# SensorPCB.net
KiCad netlist of a schematic drawn in EAGLE
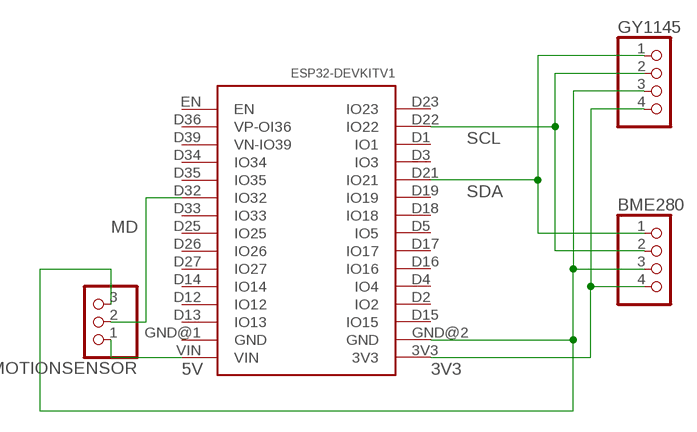
[diagram p0: schematic, sheet 1]

(export (version "E")
  (design (tool "Eeschema 10.0.6"))
  (components
    (comp (ref "BME280")
      (value "PINHD-1X4")
      (footprint "eagle-import:1X04")
      (libsource (lib "eagle-import") (part "PINHD-1X4"))
    )
    (comp (ref "GY1145")
      (value "PINHD-1X4")
      (footprint "eagle-import:1X04")
      (libsource (lib "eagle-import") (part "PINHD-1X4"))
    )
    (comp (ref "MOTIONSENSOR")
      (value "PINHD-1X3")
      (footprint "eagle-import:1X03")
      (libsource (lib "eagle-import") (part "PINHD-1X3"))
    )
    (comp (ref "U$1")
      (value "ESP32DEVKITV1")
      (footprint "eagle-import:ESP32-DEVKITV1")
      (libsource (lib "eagle-import") (part "ESP32DEVKITV1"))
    )
  )
  (nets
    (net (code "1") (name "/3V3") (class "Default")
      (node (ref "BME280") (pin "4") (pinfunction "4_4") (pintype "passive"))
      (node (ref "GY1145") (pin "4") (pinfunction "4_4") (pintype "passive"))
      (node (ref "U$1") (pin "3V3") (pinfunction "3V3_3V3") (pintype "bidirectional"))
    )
    (net (code "2") (name "/5V") (class "Default")
      (node (ref "MOTIONSENSOR") (pin "1") (pinfunction "1_1") (pintype "passive"))
      (node (ref "U$1") (pin "VIN") (pinfunction "VIN_VIN") (pintype "bidirectional"))
    )
    (net (code "3") (name "/MD") (class "Default")
      (node (ref "MOTIONSENSOR") (pin "2") (pinfunction "2_2") (pintype "passive"))
      (node (ref "U$1") (pin "D32") (pinfunction "IO32_D32") (pintype "bidirectional"))
    )
    (net (code "4") (name "/SCL") (class "Default")
      (node (ref "BME280") (pin "2") (pinfunction "2_2") (pintype "passive"))
      (node (ref "GY1145") (pin "2") (pinfunction "2_2") (pintype "passive"))
      (node (ref "U$1") (pin "D22") (pinfunction "IO22_D22") (pintype "bidirectional"))
    )
    (net (code "5") (name "/SDA") (class "Default")
      (node (ref "BME280") (pin "1") (pinfunction "1_1") (pintype "passive"))
      (node (ref "GY1145") (pin "1") (pinfunction "1_1") (pintype "passive"))
      (node (ref "U$1") (pin "D21") (pinfunction "IO21_D21") (pintype "bidirectional"))
    )
    (net (code "6") (name "Net-(BME280-Pad3)") (class "Default")
      (node (ref "BME280") (pin "3") (pinfunction "3_3") (pintype "passive"))
      (node (ref "GY1145") (pin "3") (pinfunction "3_3") (pintype "passive"))
      (node (ref "MOTIONSENSOR") (pin "3") (pinfunction "3_3") (pintype "passive"))
      (node (ref "U$1") (pin "GND@2") (pinfunction "GND_GND@2") (pintype "bidirectional"))
    )
    (net (code "7") (name "unconnected-(U$1-GND-PadGND@1)") (class "Default")
      (node (ref "U$1") (pin "GND@1") (pinfunction "GND_GND@1") (pintype "bidirectional"))
    )
    (net (code "8") (name "unconnected-(U$1-IO1-PadD1)") (class "Default")
      (node (ref "U$1") (pin "D1") (pinfunction "IO1_D1") (pintype "bidirectional"))
    )
    (net (code "9") (name "unconnected-(U$1-IO2-PadD2)") (class "Default")
      (node (ref "U$1") (pin "D2") (pinfunction "IO2_D2") (pintype "bidirectional"))
    )
    (net (code "10") (name "unconnected-(U$1-IO3-PadD3)") (class "Default")
      (node (ref "U$1") (pin "D3") (pinfunction "IO3_D3") (pintype "bidirectional"))
    )
    (net (code "11") (name "unconnected-(U$1-IO4-PadD4)") (class "Default")
      (node (ref "U$1") (pin "D4") (pinfunction "IO4_D4") (pintype "bidirectional"))
    )
    (net (code "12") (name "unconnected-(U$1-IO5-PadD5)") (class "Default")
      (node (ref "U$1") (pin "D5") (pinfunction "IO5_D5") (pintype "bidirectional"))
    )
    (net (code "13") (name "unconnected-(U$1-IO12-PadD12)") (class "Default")
      (node (ref "U$1") (pin "D12") (pinfunction "IO12_D12") (pintype "bidirectional"))
    )
    (net (code "14") (name "unconnected-(U$1-IO13-PadD13)") (class "Default")
      (node (ref "U$1") (pin "D13") (pinfunction "IO13_D13") (pintype "bidirectional"))
    )
    (net (code "15") (name "unconnected-(U$1-IO14-PadD14)") (class "Default")
      (node (ref "U$1") (pin "D14") (pinfunction "IO14_D14") (pintype "bidirectional"))
    )
    (net (code "16") (name "unconnected-(U$1-IO15-PadD15)") (class "Default")
      (node (ref "U$1") (pin "D15") (pinfunction "IO15_D15") (pintype "bidirectional"))
    )
    (net (code "17") (name "unconnected-(U$1-IO16-PadD16)") (class "Default")
      (node (ref "U$1") (pin "D16") (pinfunction "IO16_D16") (pintype "bidirectional"))
    )
    (net (code "18") (name "unconnected-(U$1-IO17-PadD17)") (class "Default")
      (node (ref "U$1") (pin "D17") (pinfunction "IO17_D17") (pintype "bidirectional"))
    )
    (net (code "19") (name "unconnected-(U$1-IO18-PadD18)") (class "Default")
      (node (ref "U$1") (pin "D18") (pinfunction "IO18_D18") (pintype "bidirectional"))
    )
    (net (code "20") (name "unconnected-(U$1-IO19-PadD19)") (class "Default")
      (node (ref "U$1") (pin "D19") (pinfunction "IO19_D19") (pintype "bidirectional"))
    )
    (net (code "21") (name "unconnected-(U$1-IO23-PadD23)") (class "Default")
      (node (ref "U$1") (pin "D23") (pinfunction "IO23_D23") (pintype "bidirectional"))
    )
    (net (code "22") (name "unconnected-(U$1-IO25-PadD25)") (class "Default")
      (node (ref "U$1") (pin "D25") (pinfunction "IO25_D25") (pintype "bidirectional"))
    )
    (net (code "23") (name "unconnected-(U$1-IO26-PadD26)") (class "Default")
      (node (ref "U$1") (pin "D26") (pinfunction "IO26_D26") (pintype "bidirectional"))
    )
    (net (code "24") (name "unconnected-(U$1-IO27-PadD27)") (class "Default")
      (node (ref "U$1") (pin "D27") (pinfunction "IO27_D27") (pintype "bidirectional"))
    )
    (net (code "25") (name "unconnected-(U$1-IO33-PadD33)") (class "Default")
      (node (ref "U$1") (pin "D33") (pinfunction "IO33_D33") (pintype "bidirectional"))
    )
    (net (code "26") (name "unconnected-(U$1-IO34-PadD34)") (class "Default")
      (node (ref "U$1") (pin "D34") (pinfunction "IO34_D34") (pintype "bidirectional"))
    )
    (net (code "27") (name "unconnected-(U$1-IO35-PadD35)") (class "Default")
      (node (ref "U$1") (pin "D35") (pinfunction "IO35_D35") (pintype "bidirectional"))
    )
    (net (code "28") (name "unconnected-(U$1-PadEN)") (class "Default")
      (node (ref "U$1") (pin "EN") (pinfunction "EN_EN") (pintype "bidirectional"))
    )
    (net (code "29") (name "unconnected-(U$1-VN-IO39-PadD39)") (class "Default")
      (node (ref "U$1") (pin "D39") (pinfunction "VN-IO39_D39") (pintype "bidirectional"))
    )
    (net (code "30") (name "unconnected-(U$1-VP-OI36-PadD36)") (class "Default")
      (node (ref "U$1") (pin "D36") (pinfunction "VP-OI36_D36") (pintype "bidirectional"))
    )
  )
)
